# 06-VOLTAGE_DETECTION.net
KiCad netlist of a schematic drawn in Altium Designer
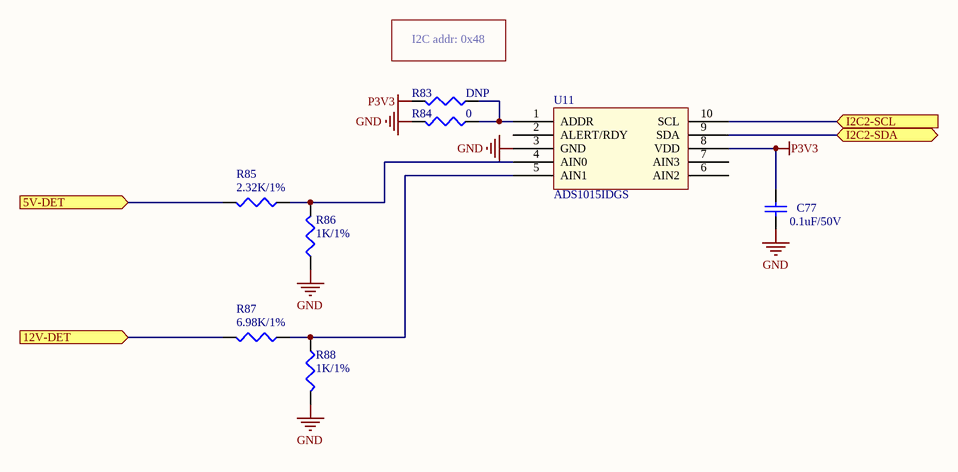
[diagram p0: 06-VOLTAGE_DETECTION.SchDoc]

(export (version "E")
  (design (tool "Eeschema 10.0.6"))
  (components
    (comp (ref "C77")
      (value "0.1uF/50V")
      (footprint "0402")
      (description "Capacitor")
      (fields (field (name "PUBLISHER") "Altium Limited"))
      (libsource (lib "Miscellaneous Devices") (part "Cap"))
    )
    (comp (ref "R83") (value "DNP") (footprint "0402") (libsource (lib "*") (part "CR16-1003FM")))
    (comp (ref "R84") (value "0") (footprint "0402") (libsource (lib "*") (part "CR16-1003FM")))
    (comp (ref "R85") (value "2.32K/1%") (footprint "0402") (libsource (lib "*") (part "CR16-1003FM")))
    (comp (ref "R86") (value "1K/1%") (footprint "0402") (libsource (lib "*") (part "CR16-1003FM")))
    (comp (ref "R87") (value "6.98K/1%") (footprint "0402") (libsource (lib "*") (part "CR16-1003FM")))
    (comp (ref "R88") (value "1K/1%") (footprint "0402") (libsource (lib "*") (part "CR16-1003FM")))
    (comp (ref "U11")
      (value "ADS1015IDGS")
      (footprint "VSSOP10")
      (libsource (lib "Schlib") (part "ADS1015IDGS"))
    )
  )
  (nets
    (net (code "1") (name "/5V-DET") (class "Default")
      (node (ref "R85") (pin "2") (pinfunction "2_2") (pintype "passive"))
    )
    (net (code "2") (name "/12V-DET") (class "Default")
      (node (ref "R87") (pin "2") (pinfunction "2_2") (pintype "passive"))
    )
    (net (code "3") (name "/I2C2-SCL") (class "Default")
      (node (ref "U11") (pin "10") (pinfunction "SCL_10") (pintype "passive"))
    )
    (net (code "4") (name "/I2C2-SDA") (class "Default")
      (node (ref "U11") (pin "9") (pinfunction "SDA_9") (pintype "passive"))
    )
    (net (code "5") (name "GND") (class "Default")
      (node (ref "C77") (pin "2") (pinfunction "2_2") (pintype "passive"))
      (node (ref "R84") (pin "2") (pinfunction "2_2") (pintype "passive"))
      (node (ref "R86") (pin "1") (pinfunction "1_1") (pintype "passive"))
      (node (ref "R88") (pin "2") (pinfunction "2_2") (pintype "passive"))
      (node (ref "U11") (pin "3") (pinfunction "GND_3") (pintype "passive"))
    )
    (net (code "6") (name "Net-(U11-ADDR)") (class "Default")
      (node (ref "R83") (pin "1") (pinfunction "1_1") (pintype "passive"))
      (node (ref "R84") (pin "1") (pinfunction "1_1") (pintype "passive"))
      (node (ref "U11") (pin "1") (pinfunction "ADDR_1") (pintype "passive"))
    )
    (net (code "7") (name "Net-(U11-AIN0)") (class "Default")
      (node (ref "R85") (pin "1") (pinfunction "1_1") (pintype "passive"))
      (node (ref "R86") (pin "2") (pinfunction "2_2") (pintype "passive"))
      (node (ref "U11") (pin "4") (pinfunction "AIN0_4") (pintype "passive"))
    )
    (net (code "8") (name "Net-(U11-AIN1)") (class "Default")
      (node (ref "R87") (pin "1") (pinfunction "1_1") (pintype "passive"))
      (node (ref "R88") (pin "1") (pinfunction "1_1") (pintype "passive"))
      (node (ref "U11") (pin "5") (pinfunction "AIN1_5") (pintype "passive"))
    )
    (net (code "9") (name "P3V3") (class "Default")
      (node (ref "C77") (pin "1") (pinfunction "1_1") (pintype "passive"))
      (node (ref "R83") (pin "2") (pinfunction "2_2") (pintype "passive"))
      (node (ref "U11") (pin "8") (pinfunction "VDD_8") (pintype "passive"))
    )
    (net (code "10") (name "unconnected-(U11-AIN2-Pad6)") (class "Default")
      (node (ref "U11") (pin "6") (pinfunction "AIN2_6") (pintype "passive"))
    )
    (net (code "11") (name "unconnected-(U11-AIN3-Pad7)") (class "Default")
      (node (ref "U11") (pin "7") (pinfunction "AIN3_7") (pintype "passive"))
    )
    (net (code "12") (name "unconnected-(U11-ALERT{slash}RDY-Pad2)") (class "Default")
      (node (ref "U11") (pin "2") (pinfunction "ALERT/RDY_2") (pintype "passive"))
    )
  )
)
